# Sheet2.net
KiCad netlist of a schematic drawn in Altium Designer
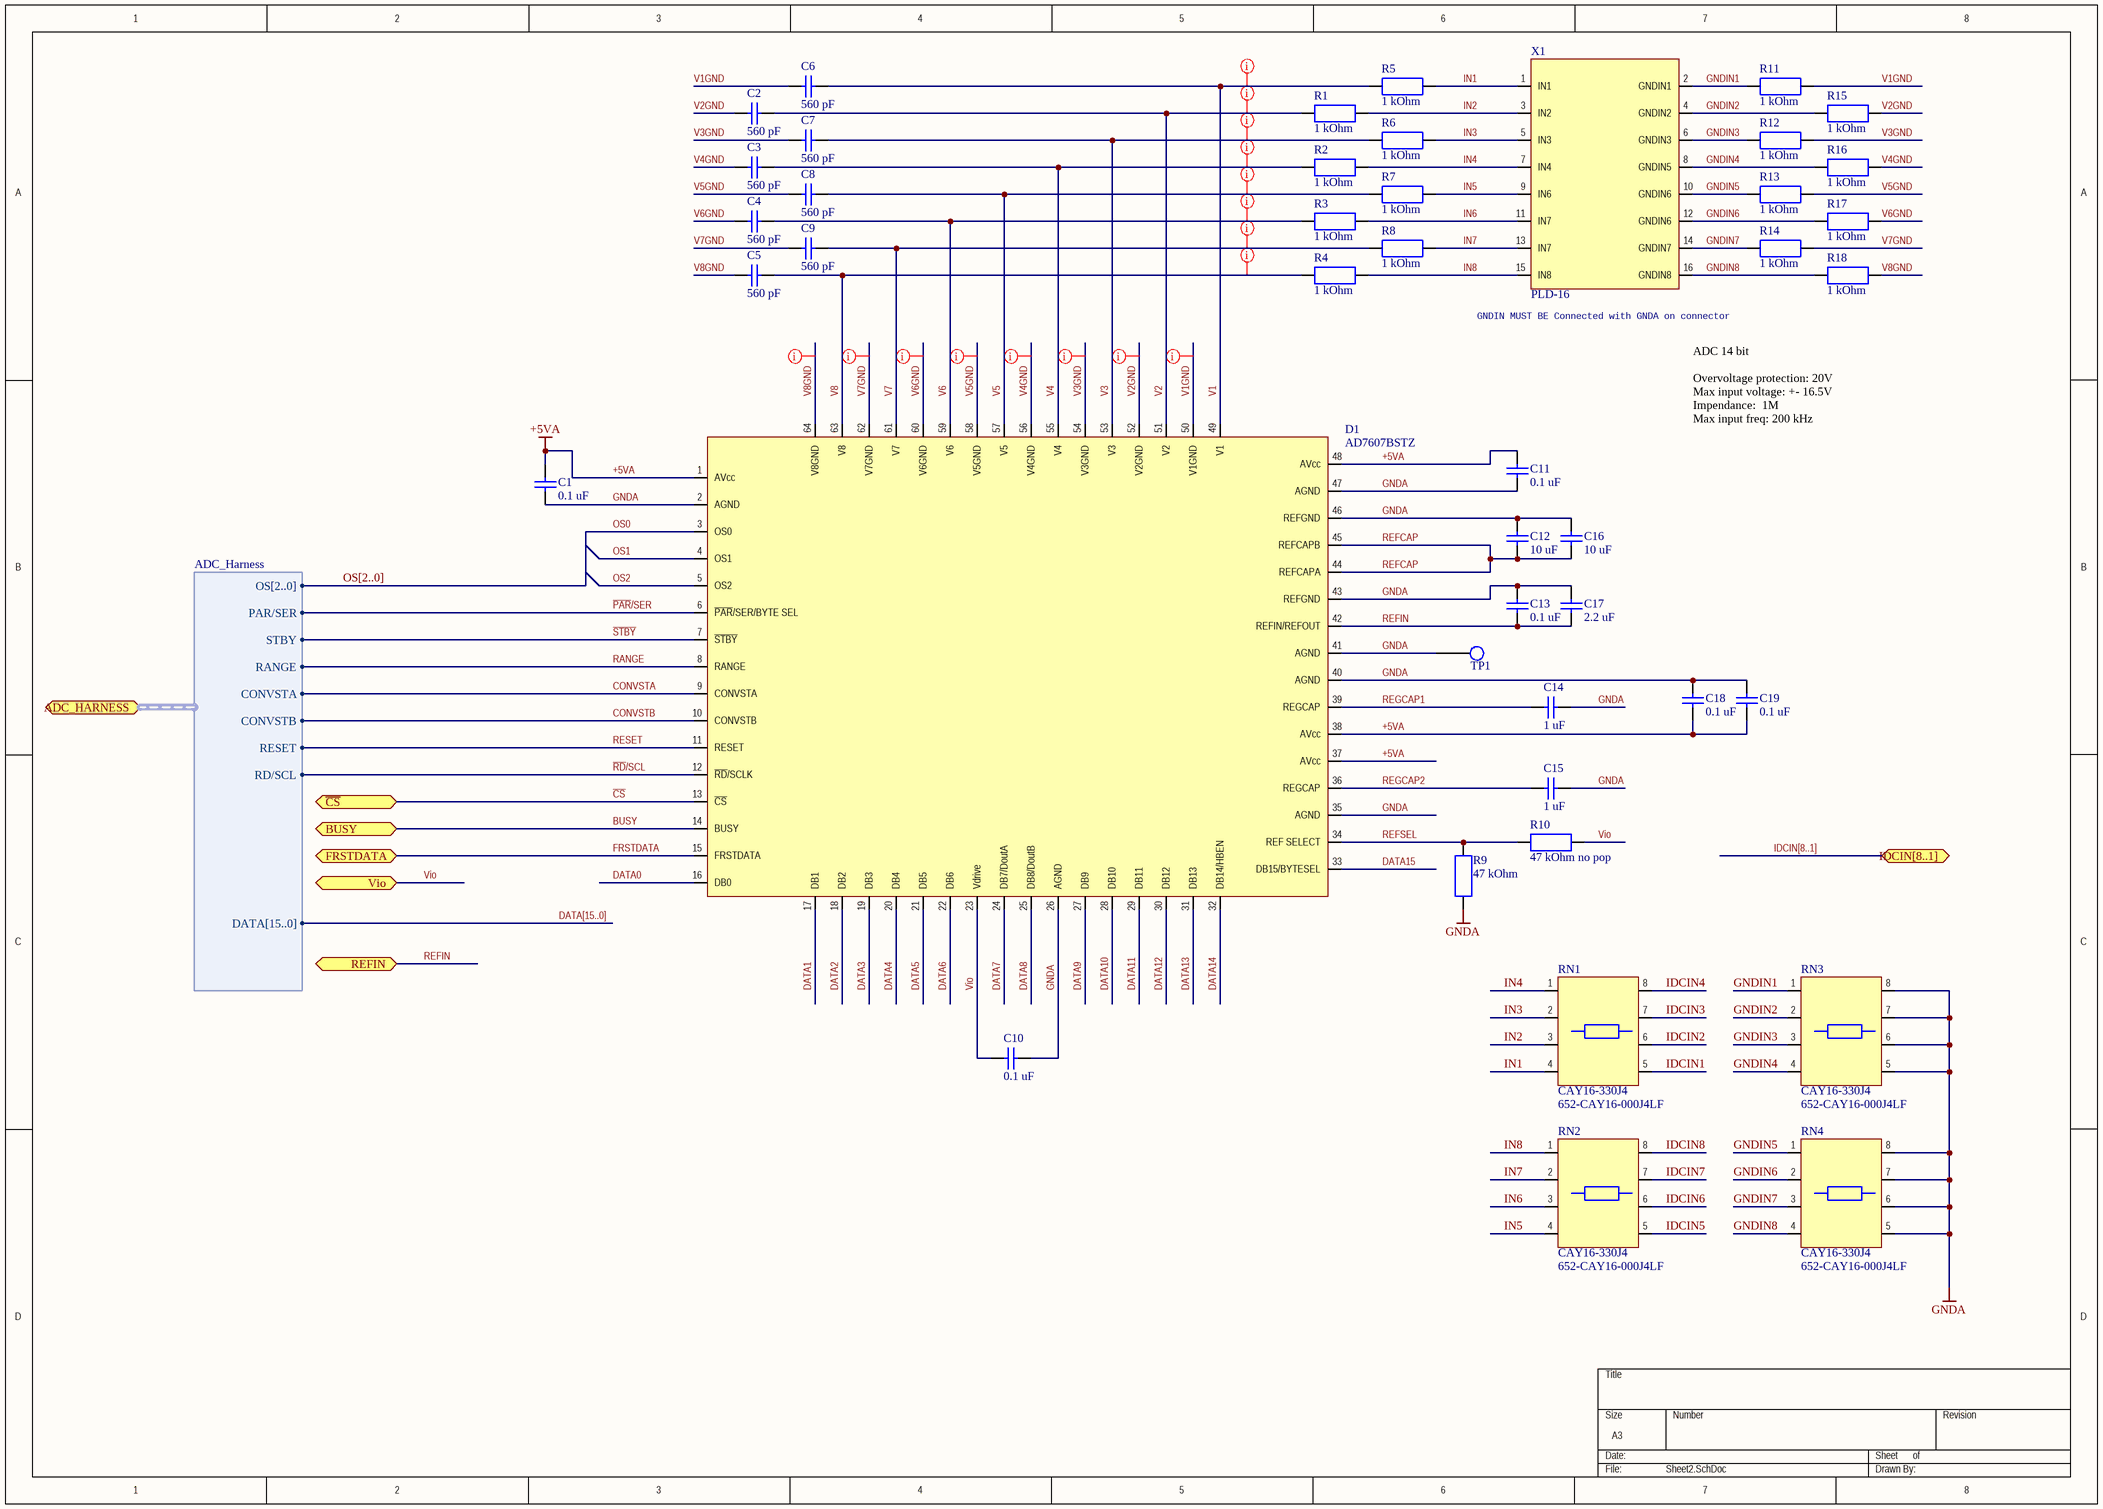
[diagram p0: Sheet2.SchDoc]

(export (version "E")
  (design (tool "Eeschema 10.0.6"))
  (components
    (comp (ref "C1")
      (value "0.1 uF")
      (footprint "CAPC1608N")
      (description "±10%, X7R, 0603")
      (fields (field (name "PUBLISHER") "DS"))
      (libsource (lib "ADClib") (part "CC0603"))
    )
    (comp (ref "C2")
      (value "560 pF")
      (footprint "CAPC1608N")
      (description "±10%, X7R, 0603")
      (fields (field (name "PUBLISHER") "DS"))
      (libsource (lib "ADClib") (part "CC0603"))
    )
    (comp (ref "C3")
      (value "560 pF")
      (footprint "CAPC1608N")
      (description "±10%, X7R, 0603")
      (fields (field (name "PUBLISHER") "DS"))
      (libsource (lib "ADClib") (part "CC0603"))
    )
    (comp (ref "C4")
      (value "560 pF")
      (footprint "CAPC1608N")
      (description "±10%, X7R, 0603")
      (fields (field (name "PUBLISHER") "DS"))
      (libsource (lib "ADClib") (part "CC0603"))
    )
    (comp (ref "C5")
      (value "560 pF")
      (footprint "CAPC1608N")
      (description "±10%, X7R, 0603")
      (fields (field (name "PUBLISHER") "DS"))
      (libsource (lib "ADClib") (part "CC0603"))
    )
    (comp (ref "C6")
      (value "560 pF")
      (footprint "CAPC1608N")
      (description "±10%, X7R, 0603")
      (fields (field (name "PUBLISHER") "DS"))
      (libsource (lib "ADClib") (part "CC0603"))
    )
    (comp (ref "C7")
      (value "560 pF")
      (footprint "CAPC1608N")
      (description "±10%, X7R, 0603")
      (fields (field (name "PUBLISHER") "DS"))
      (libsource (lib "ADClib") (part "CC0603"))
    )
    (comp (ref "C8")
      (value "560 pF")
      (footprint "CAPC1608N")
      (description "±10%, X7R, 0603")
      (fields (field (name "PUBLISHER") "DS"))
      (libsource (lib "ADClib") (part "CC0603"))
    )
    (comp (ref "C9")
      (value "560 pF")
      (footprint "CAPC1608N")
      (description "±10%, X7R, 0603")
      (fields (field (name "PUBLISHER") "DS"))
      (libsource (lib "ADClib") (part "CC0603"))
    )
    (comp (ref "C10")
      (value "0.1 uF")
      (footprint "CAPC1608N")
      (description "±10%, X7R, 0603")
      (fields (field (name "PUBLISHER") "DS"))
      (libsource (lib "ADClib") (part "CC0603"))
    )
    (comp (ref "C11")
      (value "0.1 uF")
      (footprint "CAPC1608N")
      (description "±10%, X7R, 0603")
      (fields (field (name "PUBLISHER") "DS"))
      (libsource (lib "ADClib") (part "CC0603"))
    )
    (comp (ref "C12")
      (value "10 uF")
      (footprint "CAPC1608N")
      (description "±10%, X7R, 0603")
      (fields (field (name "PUBLISHER") "DS"))
      (libsource (lib "ADClib") (part "CC0603"))
    )
    (comp (ref "C13")
      (value "0.1 uF")
      (footprint "CAPC1608N")
      (description "±10%, X7R, 0603")
      (fields (field (name "PUBLISHER") "DS"))
      (libsource (lib "ADClib") (part "CC0603"))
    )
    (comp (ref "C14")
      (value "1 uF")
      (footprint "CAPC1608N")
      (description "±10%, X7R, 0603")
      (fields (field (name "PUBLISHER") "DS"))
      (libsource (lib "ADClib") (part "CC0603"))
    )
    (comp (ref "C15")
      (value "1 uF")
      (footprint "CAPC1608N")
      (description "±10%, X7R, 0603")
      (fields (field (name "PUBLISHER") "DS"))
      (libsource (lib "ADClib") (part "CC0603"))
    )
    (comp (ref "C16")
      (value "10 uF")
      (footprint "CAPC1608N")
      (description "±10%, X7R, 0603")
      (fields (field (name "PUBLISHER") "DS"))
      (libsource (lib "ADClib") (part "CC0603"))
    )
    (comp (ref "C17")
      (value "2.2 uF")
      (footprint "CAPC1608N")
      (description "±10%, X7R, 0603")
      (fields (field (name "PUBLISHER") "DS"))
      (libsource (lib "ADClib") (part "CC0603"))
    )
    (comp (ref "C18")
      (value "0.1 uF")
      (footprint "CAPC1608N")
      (description "±10%, X7R, 0603")
      (fields (field (name "PUBLISHER") "DS"))
      (libsource (lib "ADClib") (part "CC0603"))
    )
    (comp (ref "C19")
      (value "0.1 uF")
      (footprint "CAPC1608N")
      (description "±10%, X7R, 0603")
      (fields (field (name "PUBLISHER") "DS"))
      (libsource (lib "ADClib") (part "CC0603"))
    )
    (comp (ref "D1")
      (value "AD7607BSTZ")
      (footprint "TSQFP50P1200X1200X160-64N")
      (description "AD7607BSTZ ADC Simultan")
      (libsource (lib "ADClib") (part "AD7607BSTZ"))
    )
    (comp (ref "R1")
      (value "1 kOhm")
      (footprint "RESC1608N")
      (description "±5%, 0603")
      (fields (field (name "PUBLISHER") "DS"))
      (libsource (lib "ADClib") (part "RES0603"))
    )
    (comp (ref "R2")
      (value "1 kOhm")
      (footprint "RESC1608N")
      (description "±5%, 0603")
      (fields (field (name "PUBLISHER") "DS"))
      (libsource (lib "ADClib") (part "RES0603"))
    )
    (comp (ref "R3")
      (value "1 kOhm")
      (footprint "RESC1608N")
      (description "±5%, 0603")
      (fields (field (name "PUBLISHER") "DS"))
      (libsource (lib "ADClib") (part "RES0603"))
    )
    (comp (ref "R4")
      (value "1 kOhm")
      (footprint "RESC1608N")
      (description "±5%, 0603")
      (fields (field (name "PUBLISHER") "DS"))
      (libsource (lib "ADClib") (part "RES0603"))
    )
    (comp (ref "R5")
      (value "1 kOhm")
      (footprint "RESC1608N")
      (description "±5%, 0603")
      (fields (field (name "PUBLISHER") "DS"))
      (libsource (lib "ADClib") (part "RES0603"))
    )
    (comp (ref "R6")
      (value "1 kOhm")
      (footprint "RESC1608N")
      (description "±5%, 0603")
      (fields (field (name "PUBLISHER") "DS"))
      (libsource (lib "ADClib") (part "RES0603"))
    )
    (comp (ref "R7")
      (value "1 kOhm")
      (footprint "RESC1608N")
      (description "±5%, 0603")
      (fields (field (name "PUBLISHER") "DS"))
      (libsource (lib "ADClib") (part "RES0603"))
    )
    (comp (ref "R8")
      (value "1 kOhm")
      (footprint "RESC1608N")
      (description "±5%, 0603")
      (fields (field (name "PUBLISHER") "DS"))
      (libsource (lib "ADClib") (part "RES0603"))
    )
    (comp (ref "R9")
      (value "47 kOhm")
      (footprint "RESC1608N")
      (description "±5%, 0603")
      (fields (field (name "PUBLISHER") "DS"))
      (libsource (lib "ADClib") (part "RES0603"))
    )
    (comp (ref "R10")
      (value "47 kOhm no pop")
      (footprint "RESC1608N")
      (description "±5%, 0603")
      (fields (field (name "PUBLISHER") "DS"))
      (libsource (lib "ADClib") (part "RES0603"))
    )
    (comp (ref "R11")
      (value "1 kOhm")
      (footprint "RESC1608N")
      (description "±5%, 0603")
      (fields (field (name "PUBLISHER") "DS"))
      (libsource (lib "ADClib") (part "RES0603"))
    )
    (comp (ref "R12")
      (value "1 kOhm")
      (footprint "RESC1608N")
      (description "±5%, 0603")
      (fields (field (name "PUBLISHER") "DS"))
      (libsource (lib "ADClib") (part "RES0603"))
    )
    (comp (ref "R13")
      (value "1 kOhm")
      (footprint "RESC1608N")
      (description "±5%, 0603")
      (fields (field (name "PUBLISHER") "DS"))
      (libsource (lib "ADClib") (part "RES0603"))
    )
    (comp (ref "R14")
      (value "1 kOhm")
      (footprint "RESC1608N")
      (description "±5%, 0603")
      (fields (field (name "PUBLISHER") "DS"))
      (libsource (lib "ADClib") (part "RES0603"))
    )
    (comp (ref "R15")
      (value "1 kOhm")
      (footprint "RESC1608N")
      (description "±5%, 0603")
      (fields (field (name "PUBLISHER") "DS"))
      (libsource (lib "ADClib") (part "RES0603"))
    )
    (comp (ref "R16")
      (value "1 kOhm")
      (footprint "RESC1608N")
      (description "±5%, 0603")
      (fields (field (name "PUBLISHER") "DS"))
      (libsource (lib "ADClib") (part "RES0603"))
    )
    (comp (ref "R17")
      (value "1 kOhm")
      (footprint "RESC1608N")
      (description "±5%, 0603")
      (fields (field (name "PUBLISHER") "DS"))
      (libsource (lib "ADClib") (part "RES0603"))
    )
    (comp (ref "R18")
      (value "1 kOhm")
      (footprint "RESC1608N")
      (description "±5%, 0603")
      (fields (field (name "PUBLISHER") "DS"))
      (libsource (lib "ADClib") (part "RES0603"))
    )
    (comp (ref "RN1")
      (value "CAY16-330J4")
      (footprint "EXB38V")
      (description "0 Ohm")
      (fields (field (name "SUPPLIER PART NUMBER 1") "652-CAY16-000J4LF"))
      (libsource (lib "ADClib") (part "CAY16"))
    )
    (comp (ref "RN2")
      (value "CAY16-330J4")
      (footprint "EXB38V")
      (description "0 Ohm")
      (fields (field (name "SUPPLIER PART NUMBER 1") "652-CAY16-000J4LF"))
      (libsource (lib "ADClib") (part "CAY16"))
    )
    (comp (ref "RN3")
      (value "CAY16-330J4")
      (footprint "EXB38V")
      (description "0 Ohm")
      (fields (field (name "SUPPLIER PART NUMBER 1") "652-CAY16-000J4LF"))
      (libsource (lib "ADClib") (part "CAY16"))
    )
    (comp (ref "RN4")
      (value "CAY16-330J4")
      (footprint "EXB38V")
      (description "0 Ohm")
      (fields (field (name "SUPPLIER PART NUMBER 1") "652-CAY16-000J4LF"))
      (libsource (lib "ADClib") (part "CAY16"))
    )
    (comp (ref "TP1") (value "PLS-1") (footprint "TPSW") (libsource (lib "ADClib") (part "PLS-1")))
    (comp (ref "X1")
      (value "PLD-16")
      (footprint "PLD-16")
      (description "ADC connector")
      (libsource (lib "ADClib") (part "ADCIN"))
    )
  )
  (nets
    (net (code "2") (name "+5VA") (class "Default")
      (node (ref "C1") (pin "2") (pinfunction "2_2") (pintype "passive"))
      (node (ref "C11") (pin "2") (pinfunction "2_2") (pintype "passive"))
      (node (ref "C18") (pin "1") (pinfunction "1_1") (pintype "passive"))
      (node (ref "C19") (pin "1") (pinfunction "1_1") (pintype "passive"))
      (node (ref "D1") (pin "1") (pinfunction "AVcc_1") (pintype "passive"))
      (node (ref "D1") (pin "37") (pinfunction "AVcc_37") (pintype "passive"))
      (node (ref "D1") (pin "38") (pinfunction "AVcc_38") (pintype "passive"))
      (node (ref "D1") (pin "48") (pinfunction "AVcc_48") (pintype "passive"))
    )
    (net (code "3") (name "/BUSY") (class "Default")
      (node (ref "D1") (pin "14") (pinfunction "BUSY_14") (pintype "passive"))
    )
    (net (code "4") (name "/CONVSTA") (class "Default")
      (node (ref "D1") (pin "9") (pinfunction "CONVSTA_9") (pintype "passive"))
    )
    (net (code "5") (name "/CONVSTB") (class "Default")
      (node (ref "D1") (pin "10") (pinfunction "CONVSTB_10") (pintype "passive"))
    )
    (net (code "6") (name "/DATA0") (class "Default")
      (node (ref "D1") (pin "16") (pinfunction "DB0_16") (pintype "passive"))
    )
    (net (code "7") (name "/DATA1") (class "Default")
      (node (ref "D1") (pin "17") (pinfunction "DB1_17") (pintype "passive"))
    )
    (net (code "8") (name "/DATA2") (class "Default")
      (node (ref "D1") (pin "18") (pinfunction "DB2_18") (pintype "passive"))
    )
    (net (code "9") (name "/DATA3") (class "Default")
      (node (ref "D1") (pin "19") (pinfunction "DB3_19") (pintype "passive"))
    )
    (net (code "10") (name "/DATA4") (class "Default")
      (node (ref "D1") (pin "20") (pinfunction "DB4_20") (pintype "passive"))
    )
    (net (code "11") (name "/DATA5") (class "Default")
      (node (ref "D1") (pin "21") (pinfunction "DB5_21") (pintype "passive"))
    )
    (net (code "12") (name "/DATA6") (class "Default")
      (node (ref "D1") (pin "22") (pinfunction "DB6_22") (pintype "passive"))
    )
    (net (code "13") (name "/DATA7") (class "Default")
      (node (ref "D1") (pin "24") (pinfunction "DB7/DoutA_24") (pintype "passive"))
    )
    (net (code "14") (name "/DATA8") (class "Default")
      (node (ref "D1") (pin "25") (pinfunction "DB8/DoutB_25") (pintype "passive"))
    )
    (net (code "15") (name "/DATA9") (class "Default")
      (node (ref "D1") (pin "27") (pinfunction "DB9_27") (pintype "passive"))
    )
    (net (code "16") (name "/DATA10") (class "Default")
      (node (ref "D1") (pin "28") (pinfunction "DB10_28") (pintype "passive"))
    )
    (net (code "17") (name "/DATA11") (class "Default")
      (node (ref "D1") (pin "29") (pinfunction "DB11_29") (pintype "passive"))
    )
    (net (code "18") (name "/DATA12") (class "Default")
      (node (ref "D1") (pin "30") (pinfunction "DB12_30") (pintype "passive"))
    )
    (net (code "19") (name "/DATA13") (class "Default")
      (node (ref "D1") (pin "31") (pinfunction "DB13_31") (pintype "passive"))
    )
    (net (code "20") (name "/DATA14") (class "Default")
      (node (ref "D1") (pin "32") (pinfunction "DB14/HBEN_32") (pintype "passive"))
    )
    (net (code "21") (name "/DATA15") (class "Default")
      (node (ref "D1") (pin "33") (pinfunction "DB15/BYTESEL_33") (pintype "passive"))
    )
    (net (code "23") (name "/FRSTDATA") (class "Default")
      (node (ref "D1") (pin "15") (pinfunction "FRSTDATA_15") (pintype "passive"))
    )
    (net (code "24") (name "/GNDIN1") (class "Default")
      (node (ref "R11") (pin "1") (pinfunction "1_1") (pintype "passive"))
      (node (ref "RN3") (pin "1") (pinfunction "1_1") (pintype "passive"))
      (node (ref "X1") (pin "2") (pinfunction "GNDIN1_2") (pintype "passive"))
    )
    (net (code "25") (name "/GNDIN2") (class "Default")
      (node (ref "R15") (pin "1") (pinfunction "1_1") (pintype "passive"))
      (node (ref "RN3") (pin "2") (pinfunction "2_2") (pintype "passive"))
      (node (ref "X1") (pin "4") (pinfunction "GNDIN2_4") (pintype "passive"))
    )
    (net (code "26") (name "/GNDIN3") (class "Default")
      (node (ref "R12") (pin "1") (pinfunction "1_1") (pintype "passive"))
      (node (ref "RN3") (pin "3") (pinfunction "3_3") (pintype "passive"))
      (node (ref "X1") (pin "6") (pinfunction "GNDIN3_6") (pintype "passive"))
    )
    (net (code "27") (name "/GNDIN4") (class "Default")
      (node (ref "R16") (pin "1") (pinfunction "1_1") (pintype "passive"))
      (node (ref "RN3") (pin "4") (pinfunction "4_4") (pintype "passive"))
      (node (ref "X1") (pin "8") (pinfunction "GNDIN5_8") (pintype "passive"))
    )
    (net (code "28") (name "/GNDIN5") (class "Default")
      (node (ref "R13") (pin "1") (pinfunction "1_1") (pintype "passive"))
      (node (ref "RN4") (pin "1") (pinfunction "1_1") (pintype "passive"))
      (node (ref "X1") (pin "10") (pinfunction "GNDIN6_10") (pintype "passive"))
    )
    (net (code "29") (name "/GNDIN6") (class "Default")
      (node (ref "R17") (pin "1") (pinfunction "1_1") (pintype "passive"))
      (node (ref "RN4") (pin "2") (pinfunction "2_2") (pintype "passive"))
      (node (ref "X1") (pin "12") (pinfunction "GNDIN6_12") (pintype "passive"))
    )
    (net (code "30") (name "/GNDIN7") (class "Default")
      (node (ref "R14") (pin "1") (pinfunction "1_1") (pintype "passive"))
      (node (ref "RN4") (pin "3") (pinfunction "3_3") (pintype "passive"))
      (node (ref "X1") (pin "14") (pinfunction "GNDIN7_14") (pintype "passive"))
    )
    (net (code "31") (name "/GNDIN8") (class "Default")
      (node (ref "R18") (pin "1") (pinfunction "1_1") (pintype "passive"))
      (node (ref "RN4") (pin "4") (pinfunction "4_4") (pintype "passive"))
      (node (ref "X1") (pin "16") (pinfunction "GNDIN8_16") (pintype "passive"))
    )
    (net (code "32") (name "/IDCIN1") (class "Default")
      (node (ref "RN1") (pin "5") (pinfunction "5_5") (pintype "passive"))
    )
    (net (code "33") (name "/IDCIN2") (class "Default")
      (node (ref "RN1") (pin "6") (pinfunction "6_6") (pintype "passive"))
    )
    (net (code "34") (name "/IDCIN3") (class "Default")
      (node (ref "RN1") (pin "7") (pinfunction "7_7") (pintype "passive"))
    )
    (net (code "35") (name "/IDCIN4") (class "Default")
      (node (ref "RN1") (pin "8") (pinfunction "8_8") (pintype "passive"))
    )
    (net (code "36") (name "/IDCIN5") (class "Default")
      (node (ref "RN2") (pin "5") (pinfunction "5_5") (pintype "passive"))
    )
    (net (code "37") (name "/IDCIN6") (class "Default")
      (node (ref "RN2") (pin "6") (pinfunction "6_6") (pintype "passive"))
    )
    (net (code "38") (name "/IDCIN7") (class "Default")
      (node (ref "RN2") (pin "7") (pinfunction "7_7") (pintype "passive"))
    )
    (net (code "39") (name "/IDCIN8") (class "Default")
      (node (ref "RN2") (pin "8") (pinfunction "8_8") (pintype "passive"))
    )
    (net (code "41") (name "/IN1") (class "Default")
      (node (ref "R5") (pin "1") (pinfunction "1_1") (pintype "passive"))
      (node (ref "RN1") (pin "4") (pinfunction "4_4") (pintype "passive"))
      (node (ref "X1") (pin "1") (pinfunction "IN1_1") (pintype "passive"))
    )
    (net (code "42") (name "/IN2") (class "Default")
      (node (ref "R1") (pin "1") (pinfunction "1_1") (pintype "passive"))
      (node (ref "RN1") (pin "3") (pinfunction "3_3") (pintype "passive"))
      (node (ref "X1") (pin "3") (pinfunction "IN2_3") (pintype "passive"))
    )
    (net (code "43") (name "/IN3") (class "Default")
      (node (ref "R6") (pin "1") (pinfunction "1_1") (pintype "passive"))
      (node (ref "RN1") (pin "2") (pinfunction "2_2") (pintype "passive"))
      (node (ref "X1") (pin "5") (pinfunction "IN3_5") (pintype "passive"))
    )
    (net (code "44") (name "/IN4") (class "Default")
      (node (ref "R2") (pin "1") (pinfunction "1_1") (pintype "passive"))
      (node (ref "RN1") (pin "1") (pinfunction "1_1") (pintype "passive"))
      (node (ref "X1") (pin "7") (pinfunction "IN4_7") (pintype "passive"))
    )
    (net (code "45") (name "/IN5") (class "Default")
      (node (ref "R7") (pin "1") (pinfunction "1_1") (pintype "passive"))
      (node (ref "RN2") (pin "4") (pinfunction "4_4") (pintype "passive"))
      (node (ref "X1") (pin "9") (pinfunction "IN6_9") (pintype "passive"))
    )
    (net (code "46") (name "/IN6") (class "Default")
      (node (ref "R3") (pin "1") (pinfunction "1_1") (pintype "passive"))
      (node (ref "RN2") (pin "3") (pinfunction "3_3") (pintype "passive"))
      (node (ref "X1") (pin "11") (pinfunction "IN7_11") (pintype "passive"))
    )
    (net (code "47") (name "/IN7") (class "Default")
      (node (ref "R8") (pin "1") (pinfunction "1_1") (pintype "passive"))
      (node (ref "RN2") (pin "2") (pinfunction "2_2") (pintype "passive"))
      (node (ref "X1") (pin "13") (pinfunction "IN7_13") (pintype "passive"))
    )
    (net (code "48") (name "/IN8") (class "Default")
      (node (ref "R4") (pin "1") (pinfunction "1_1") (pintype "passive"))
      (node (ref "RN2") (pin "1") (pinfunction "1_1") (pintype "passive"))
      (node (ref "X1") (pin "15") (pinfunction "IN8_15") (pintype "passive"))
    )
    (net (code "49") (name "/OS0") (class "Default")
      (node (ref "D1") (pin "3") (pinfunction "OS0_3") (pintype "passive"))
    )
    (net (code "50") (name "/OS1") (class "Default")
      (node (ref "D1") (pin "4") (pinfunction "OS1_4") (pintype "passive"))
    )
    (net (code "51") (name "/OS2") (class "Default")
      (node (ref "D1") (pin "5") (pinfunction "OS2_5") (pintype "passive"))
    )
    (net (code "53") (name "/RANGE") (class "Default")
      (node (ref "D1") (pin "8") (pinfunction "RANGE_8") (pintype "passive"))
    )
    (net (code "54") (name "/REFCAP") (class "Default")
      (node (ref "C12") (pin "1") (pinfunction "1_1") (pintype "passive"))
      (node (ref "C16") (pin "1") (pinfunction "1_1") (pintype "passive"))
      (node (ref "D1") (pin "44") (pinfunction "REFCAPA_44") (pintype "passive"))
      (node (ref "D1") (pin "45") (pinfunction "REFCAPB_45") (pintype "passive"))
    )
    (net (code "55") (name "/REFIN") (class "Default")
      (node (ref "C13") (pin "1") (pinfunction "1_1") (pintype "passive"))
      (node (ref "C17") (pin "1") (pinfunction "1_1") (pintype "passive"))
      (node (ref "D1") (pin "42") (pinfunction "REFIN/REFOUT_42") (pintype "passive"))
    )
    (net (code "56") (name "/REFSEL") (class "Default")
      (node (ref "D1") (pin "34") (pinfunction "REF_SELECT_34") (pintype "passive"))
      (node (ref "R10") (pin "2") (pinfunction "2_2") (pintype "passive"))
      (node (ref "R9") (pin "2") (pinfunction "2_2") (pintype "passive"))
    )
    (net (code "57") (name "/REGCAP1") (class "Default")
      (node (ref "C14") (pin "2") (pinfunction "2_2") (pintype "passive"))
      (node (ref "D1") (pin "39") (pinfunction "REGCAP_39") (pintype "passive"))
    )
    (net (code "58") (name "/REGCAP2") (class "Default")
      (node (ref "C15") (pin "2") (pinfunction "2_2") (pintype "passive"))
      (node (ref "D1") (pin "36") (pinfunction "REGCAP_36") (pintype "passive"))
    )
    (net (code "59") (name "/RESET") (class "Default")
      (node (ref "D1") (pin "11") (pinfunction "RESET_11") (pintype "passive"))
    )
    (net (code "60") (name "/V1") (class "Default")
      (node (ref "C6") (pin "2") (pinfunction "2_2") (pintype "passive"))
      (node (ref "D1") (pin "49") (pinfunction "V1_49") (pintype "passive"))
      (node (ref "R5") (pin "2") (pinfunction "2_2") (pintype "passive"))
    )
    (net (code "61") (name "/V1GND") (class "Default")
      (node (ref "C6") (pin "1") (pinfunction "1_1") (pintype "passive"))
      (node (ref "D1") (pin "50") (pinfunction "V1GND_50") (pintype "passive"))
      (node (ref "R11") (pin "2") (pinfunction "2_2") (pintype "passive"))
    )
    (net (code "62") (name "/V2") (class "Default")
      (node (ref "C2") (pin "2") (pinfunction "2_2") (pintype "passive"))
      (node (ref "D1") (pin "51") (pinfunction "V2_51") (pintype "passive"))
      (node (ref "R1") (pin "2") (pinfunction "2_2") (pintype "passive"))
    )
    (net (code "63") (name "/V2GND") (class "Default")
      (node (ref "C2") (pin "1") (pinfunction "1_1") (pintype "passive"))
      (node (ref "D1") (pin "52") (pinfunction "V2GND_52") (pintype "passive"))
      (node (ref "R15") (pin "2") (pinfunction "2_2") (pintype "passive"))
    )
    (net (code "64") (name "/V3") (class "Default")
      (node (ref "C7") (pin "2") (pinfunction "2_2") (pintype "passive"))
      (node (ref "D1") (pin "53") (pinfunction "V3_53") (pintype "passive"))
      (node (ref "R6") (pin "2") (pinfunction "2_2") (pintype "passive"))
    )
    (net (code "65") (name "/V3GND") (class "Default")
      (node (ref "C7") (pin "1") (pinfunction "1_1") (pintype "passive"))
      (node (ref "D1") (pin "54") (pinfunction "V3GND_54") (pintype "passive"))
      (node (ref "R12") (pin "2") (pinfunction "2_2") (pintype "passive"))
    )
    (net (code "66") (name "/V4") (class "Default")
      (node (ref "C3") (pin "2") (pinfunction "2_2") (pintype "passive"))
      (node (ref "D1") (pin "55") (pinfunction "V4_55") (pintype "passive"))
      (node (ref "R2") (pin "2") (pinfunction "2_2") (pintype "passive"))
    )
    (net (code "67") (name "/V4GND") (class "Default")
      (node (ref "C3") (pin "1") (pinfunction "1_1") (pintype "passive"))
      (node (ref "D1") (pin "56") (pinfunction "V4GND_56") (pintype "passive"))
      (node (ref "R16") (pin "2") (pinfunction "2_2") (pintype "passive"))
    )
    (net (code "68") (name "/V5") (class "Default")
      (node (ref "C8") (pin "2") (pinfunction "2_2") (pintype "passive"))
      (node (ref "D1") (pin "57") (pinfunction "V5_57") (pintype "passive"))
      (node (ref "R7") (pin "2") (pinfunction "2_2") (pintype "passive"))
    )
    (net (code "69") (name "/V5GND") (class "Default")
      (node (ref "C8") (pin "1") (pinfunction "1_1") (pintype "passive"))
      (node (ref "D1") (pin "58") (pinfunction "V5GND_58") (pintype "passive"))
      (node (ref "R13") (pin "2") (pinfunction "2_2") (pintype "passive"))
    )
    (net (code "70") (name "/V6") (class "Default")
      (node (ref "C4") (pin "2") (pinfunction "2_2") (pintype "passive"))
      (node (ref "D1") (pin "59") (pinfunction "V6_59") (pintype "passive"))
      (node (ref "R3") (pin "2") (pinfunction "2_2") (pintype "passive"))
    )
    (net (code "71") (name "/V6GND") (class "Default")
      (node (ref "C4") (pin "1") (pinfunction "1_1") (pintype "passive"))
      (node (ref "D1") (pin "60") (pinfunction "V6GND_60") (pintype "passive"))
      (node (ref "R17") (pin "2") (pinfunction "2_2") (pintype "passive"))
    )
    (net (code "72") (name "/V7") (class "Default")
      (node (ref "C9") (pin "2") (pinfunction "2_2") (pintype "passive"))
      (node (ref "D1") (pin "61") (pinfunction "V7_61") (pintype "passive"))
      (node (ref "R8") (pin "2") (pinfunction "2_2") (pintype "passive"))
    )
    (net (code "73") (name "/V7GND") (class "Default")
      (node (ref "C9") (pin "1") (pinfunction "1_1") (pintype "passive"))
      (node (ref "D1") (pin "62") (pinfunction "V7GND_62") (pintype "passive"))
      (node (ref "R14") (pin "2") (pinfunction "2_2") (pintype "passive"))
    )
    (net (code "74") (name "/V8") (class "Default")
      (node (ref "C5") (pin "2") (pinfunction "2_2") (pintype "passive"))
      (node (ref "D1") (pin "63") (pinfunction "V8_63") (pintype "passive"))
      (node (ref "R4") (pin "2") (pinfunction "2_2") (pintype "passive"))
    )
    (net (code "75") (name "/V8GND") (class "Default")
      (node (ref "C5") (pin "1") (pinfunction "1_1") (pintype "passive"))
      (node (ref "D1") (pin "64") (pinfunction "V8GND_64") (pintype "passive"))
      (node (ref "R18") (pin "2") (pinfunction "2_2") (pintype "passive"))
    )
    (net (code "76") (name "/Vio") (class "Default")
      (node (ref "C10") (pin "2") (pinfunction "2_2") (pintype "passive"))
      (node (ref "D1") (pin "23") (pinfunction "Vdrive_23") (pintype "passive"))
      (node (ref "R10") (pin "1") (pinfunction "1_1") (pintype "passive"))
    )
    (net (code "78") (name "/~{CS}") (class "Default")
      (node (ref "D1") (pin "13") (pinfunction "~{CS}_13") (pintype "passive"))
    )
    (net (code "79") (name "/~{PAR}{slash}SER") (class "Default")
      (node (ref "D1") (pin "6") (pinfunction "~{PAR}/SER/BYTE_SEL_6") (pintype "passive"))
    )
    (net (code "80") (name "/~{RD}{slash}SCL") (class "Default")
      (node (ref "D1") (pin "12") (pinfunction "~{RD}/SCLK_12") (pintype "passive"))
    )
    (net (code "81") (name "/~{STBY}") (class "Default")
      (node (ref "D1") (pin "7") (pinfunction "~{STBY}_7") (pintype "passive"))
    )
    (net (code "82") (name "GNDA") (class "Default")
      (node (ref "C1") (pin "1") (pinfunction "1_1") (pintype "passive"))
      (node (ref "C10") (pin "1") (pinfunction "1_1") (pintype "passive"))
      (node (ref "C11") (pin "1") (pinfunction "1_1") (pintype "passive"))
      (node (ref "C12") (pin "2") (pinfunction "2_2") (pintype "passive"))
      (node (ref "C13") (pin "2") (pinfunction "2_2") (pintype "passive"))
      (node (ref "C14") (pin "1") (pinfunction "1_1") (pintype "passive"))
      (node (ref "C15") (pin "1") (pinfunction "1_1") (pintype "passive"))
      (node (ref "C16") (pin "2") (pinfunction "2_2") (pintype "passive"))
      (node (ref "C17") (pin "2") (pinfunction "2_2") (pintype "passive"))
      (node (ref "C18") (pin "2") (pinfunction "2_2") (pintype "passive"))
      (node (ref "C19") (pin "2") (pinfunction "2_2") (pintype "passive"))
      (node (ref "D1") (pin "2") (pinfunction "AGND_2") (pintype "passive"))
      (node (ref "D1") (pin "26") (pinfunction "AGND_26") (pintype "passive"))
      (node (ref "D1") (pin "35") (pinfunction "AGND_35") (pintype "passive"))
      (node (ref "D1") (pin "40") (pinfunction "AGND_40") (pintype "passive"))
      (node (ref "D1") (pin "41") (pinfunction "AGND_41") (pintype "passive"))
      (node (ref "D1") (pin "43") (pinfunction "REFGND_43") (pintype "passive"))
      (node (ref "D1") (pin "46") (pinfunction "REFGND_46") (pintype "passive"))
      (node (ref "D1") (pin "47") (pinfunction "AGND_47") (pintype "passive"))
      (node (ref "R9") (pin "1") (pinfunction "1_1") (pintype "passive"))
      (node (ref "RN3") (pin "5") (pinfunction "5_5") (pintype "passive"))
      (node (ref "RN3") (pin "6") (pinfunction "6_6") (pintype "passive"))
      (node (ref "RN3") (pin "7") (pinfunction "7_7") (pintype "passive"))
      (node (ref "RN3") (pin "8") (pinfunction "8_8") (pintype "passive"))
      (node (ref "RN4") (pin "5") (pinfunction "5_5") (pintype "passive"))
      (node (ref "RN4") (pin "6") (pinfunction "6_6") (pintype "passive"))
      (node (ref "RN4") (pin "7") (pinfunction "7_7") (pintype "passive"))
      (node (ref "RN4") (pin "8") (pinfunction "8_8") (pintype "passive"))
      (node (ref "TP1") (pin "1") (pinfunction "1_1") (pintype "passive"))
    )
  )
)
